# 1-RF.net
KiCad netlist of a schematic drawn in Altium Designer
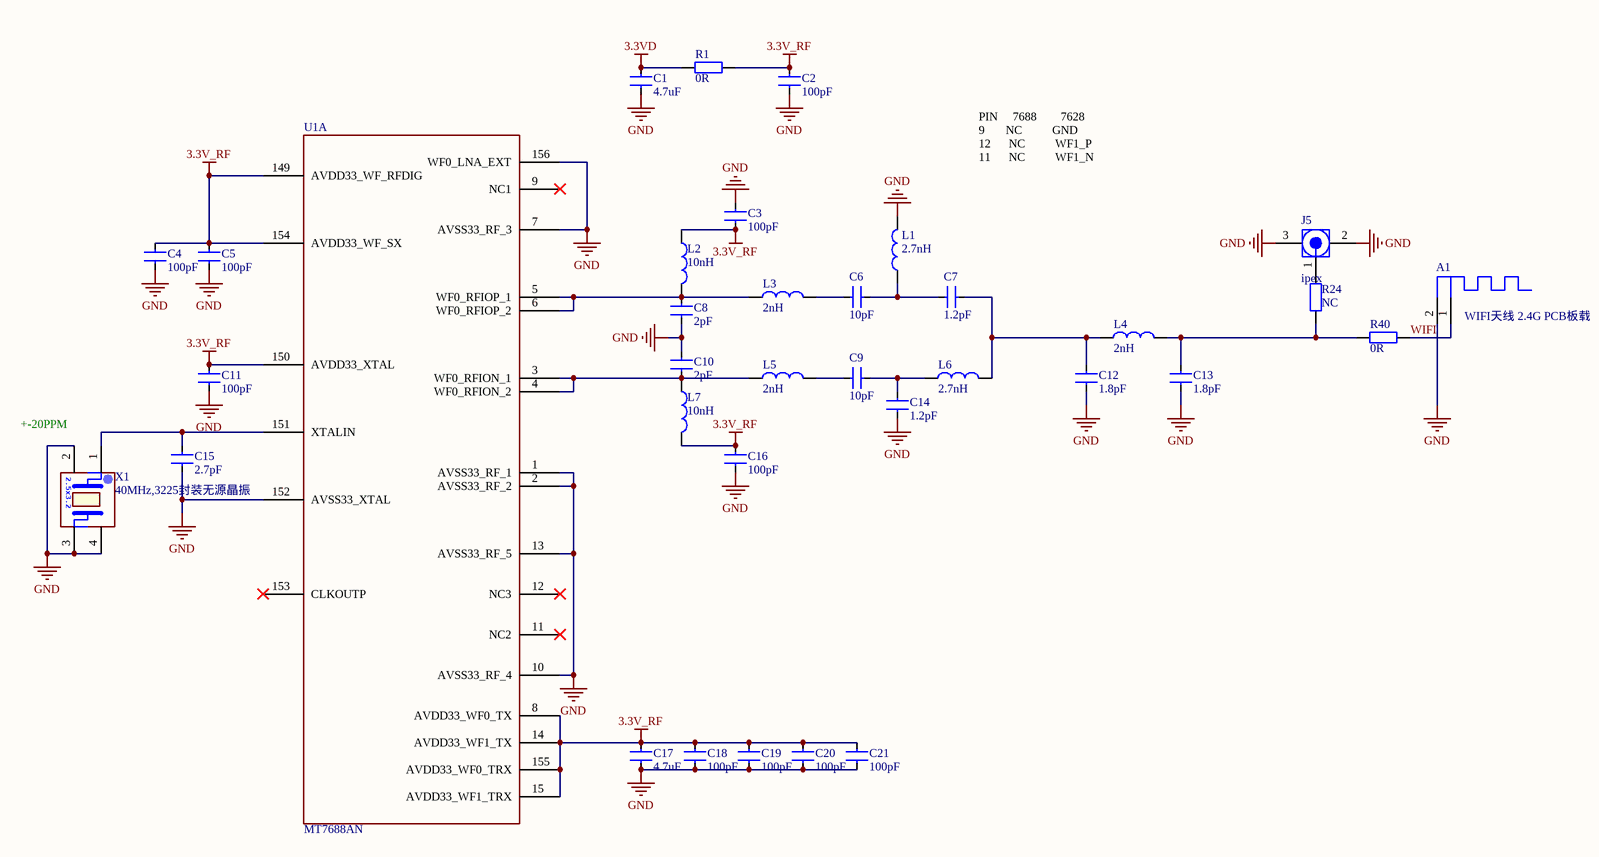
[diagram p0: 1-RF.SchDoc]

(export (version "E")
  (design (tool "Eeschema 10.0.6"))
  (components
    (comp (ref "A1")
      (value "WIFI天线 2.4G PCB板载")
      (footprint "2.4G - mirror")
      (libsource (lib "LIB_MANGO") (part "ANT2.4G"))
    )
    (comp (ref "C1")
      (value "4.7uF")
      (footprint "C0402")
      (description "普通小电容")
      (libsource (lib "LIB_MANGO") (part "CAP"))
    )
    (comp (ref "C2")
      (value "100pF")
      (footprint "C0402")
      (description "普通小电容")
      (libsource (lib "LIB_MANGO") (part "CAP"))
    )
    (comp (ref "C3")
      (value "100pF")
      (footprint "C0402")
      (description "普通小电容")
      (libsource (lib "LIB_MANGO") (part "CAP"))
    )
    (comp (ref "C4")
      (value "100pF")
      (footprint "C0402")
      (description "普通小电容")
      (libsource (lib "LIB_MANGO") (part "CAP"))
    )
    (comp (ref "C5")
      (value "100pF")
      (footprint "C0402")
      (description "普通小电容")
      (libsource (lib "LIB_MANGO") (part "CAP"))
    )
    (comp (ref "C6")
      (value "10pF")
      (footprint "C0402")
      (description "GRM1555C1H100JA01D,500R07N100JV4")
      (libsource (lib "LIB_MANGO") (part "CAP"))
    )
    (comp (ref "C7")
      (value "1.2pF")
      (footprint "C0402")
      (description "GRM1555C1H1R2CA01D,500R07N1R2CV4")
      (libsource (lib "LIB_MANGO") (part "CAP"))
    )
    (comp (ref "C8")
      (value "2pF")
      (footprint "C0402")
      (description "GRM1555C1H2R0CA01D,500R07N2R0CV4")
      (libsource (lib "LIB_MANGO") (part "CAP"))
    )
    (comp (ref "C9")
      (value "10pF")
      (footprint "C0402")
      (description "GRM1555C1H100JA01D,500R07N100JV4")
      (libsource (lib "LIB_MANGO") (part "CAP"))
    )
    (comp (ref "C10")
      (value "2pF")
      (footprint "C0402")
      (description "GRM1555C1H2R0CA01D,500R07N2R0CV4")
      (libsource (lib "LIB_MANGO") (part "CAP"))
    )
    (comp (ref "C11")
      (value "100pF")
      (footprint "C0402")
      (description "普通小电容")
      (libsource (lib "LIB_MANGO") (part "CAP"))
    )
    (comp (ref "C12")
      (value "1.8pF")
      (footprint "C0402")
      (description "GRM1555C1H1R8CA01D")
      (libsource (lib "LIB_MANGO") (part "CAP"))
    )
    (comp (ref "C13")
      (value "1.8pF")
      (footprint "C0402")
      (description "GRM1555C1H1R8CA01D")
      (libsource (lib "LIB_MANGO") (part "CAP"))
    )
    (comp (ref "C14")
      (value "1.2pF")
      (footprint "C0402")
      (description "GRM1555C1H1R2CA01D,500R07N1R2CV4")
      (libsource (lib "LIB_MANGO") (part "CAP"))
    )
    (comp (ref "C15")
      (value "2.7pF")
      (footprint "C0402")
      (description "普通小电容")
      (libsource (lib "LIB_MANGO") (part "CAP"))
    )
    (comp (ref "C16")
      (value "100pF")
      (footprint "C0402")
      (description "普通小电容")
      (libsource (lib "LIB_MANGO") (part "CAP"))
    )
    (comp (ref "C17")
      (value "4.7uF")
      (footprint "C0402")
      (description "普通小电容")
      (libsource (lib "LIB_MANGO") (part "CAP"))
    )
    (comp (ref "C18")
      (value "100pF")
      (footprint "C0402")
      (description "普通小电容")
      (libsource (lib "LIB_MANGO") (part "CAP"))
    )
    (comp (ref "C19")
      (value "100pF")
      (footprint "C0402")
      (description "普通小电容")
      (libsource (lib "LIB_MANGO") (part "CAP"))
    )
    (comp (ref "C20")
      (value "100pF")
      (footprint "C0402")
      (description "普通小电容")
      (libsource (lib "LIB_MANGO") (part "CAP"))
    )
    (comp (ref "C21")
      (value "100pF")
      (footprint "C0402")
      (description "普通小电容")
      (libsource (lib "LIB_MANGO") (part "CAP"))
    )
    (comp (ref "J5") (value "ipex") (footprint "IPEX") (libsource (lib "LIB_MANGO") (part "MCX_IPEX")))
    (comp (ref "L1")
      (value "2.7nH")
      (footprint "L0402")
      (description "LQG15HS2N7S02,MLG1005S2N7ST")
      (libsource (lib "") (part "L0402_1"))
    )
    (comp (ref "L2")
      (value "10nH")
      (footprint "L0402")
      (description "LQG15HS10NJ02,MLG1005S10NJT,HI1005-1C10NJMT")
      (libsource (lib "") (part "L0402_1"))
    )
    (comp (ref "L3")
      (value "2nH")
      (footprint "L0402")
      (description "LQG15HS2N0S02")
      (libsource (lib "LIB_MANGO") (part "L0402"))
    )
    (comp (ref "L4")
      (value "2nH")
      (footprint "L0402")
      (description "LQG15HS2N0S02")
      (libsource (lib "LIB_MANGO") (part "L0402"))
    )
    (comp (ref "L5")
      (value "2nH")
      (footprint "L0402")
      (description "LQG15HS2N0S02")
      (libsource (lib "LIB_MANGO") (part "L0402"))
    )
    (comp (ref "L6")
      (value "2.7nH")
      (footprint "L0402")
      (description "LQG15HS2N7S02,MLG1005S2N7ST")
      (libsource (lib "LIB_MANGO") (part "L0402"))
    )
    (comp (ref "L7")
      (value "10nH")
      (footprint "L0402")
      (description "LQG15HS10NJ02,MLG1005S10NJT,HI1005-1C10NJMT")
      (libsource (lib "") (part "L0402_1"))
    )
    (comp (ref "R1")
      (value "0R")
      (footprint "R0402")
      (description "普通电阻")
      (libsource (lib "LIB_MANGO") (part "RES"))
    )
    (comp (ref "R24")
      (value "NC")
      (footprint "R0402")
      (description "普通电阻")
      (libsource (lib "") (part "RES_1"))
    )
    (comp (ref "R40")
      (value "0R")
      (footprint "R0402")
      (description "普通电阻")
      (libsource (lib "LIB_MANGO") (part "RES"))
    )
    (comp (ref "U1")
      (value "MT7688AN")
      (footprint "MT7628AN/DRQFN156/SMD/P0.5/12X12")
      (libsource (lib "A") (part "MT7688AN"))
    )
    (comp (ref "X1")
      (value "40MHz,3225封装无源晶振")
      (footprint "XTAL3225")
      (description "贴片晶振")
      (libsource (lib "RCLD") (part "XTAL3225"))
    )
  )
  (nets
    (net (code "1") (name "/WIFI") (class "Default")
      (node (ref "A1") (pin "1") (pintype "passive"))
      (node (ref "R40") (pin "2") (pinfunction "2_2") (pintype "passive"))
    )
    (net (code "2") (name "3.3VD") (class "Default")
      (node (ref "C1") (pin "1") (pinfunction "1_1") (pintype "passive"))
      (node (ref "R1") (pin "1") (pinfunction "1_1") (pintype "passive"))
    )
    (net (code "3") (name "3.3V_RF") (class "Default")
      (node (ref "C11") (pin "1") (pinfunction "1_1") (pintype "passive"))
      (node (ref "C16") (pin "1") (pinfunction "1_1") (pintype "passive"))
      (node (ref "C17") (pin "1") (pinfunction "1_1") (pintype "passive"))
      (node (ref "C18") (pin "1") (pinfunction "1_1") (pintype "passive"))
      (node (ref "C19") (pin "1") (pinfunction "1_1") (pintype "passive"))
      (node (ref "C2") (pin "1") (pinfunction "1_1") (pintype "passive"))
      (node (ref "C20") (pin "1") (pinfunction "1_1") (pintype "passive"))
      (node (ref "C21") (pin "1") (pinfunction "1_1") (pintype "passive"))
      (node (ref "C3") (pin "2") (pinfunction "2_2") (pintype "passive"))
      (node (ref "C4") (pin "1") (pinfunction "1_1") (pintype "passive"))
      (node (ref "C5") (pin "1") (pinfunction "1_1") (pintype "passive"))
      (node (ref "L2") (pin "2") (pinfunction "2_2") (pintype "passive"))
      (node (ref "L7") (pin "1") (pinfunction "1_1") (pintype "passive"))
      (node (ref "R1") (pin "2") (pinfunction "2_2") (pintype "passive"))
      (node (ref "U1") (pin "14") (pinfunction "AVDD33_WF1_TX_14") (pintype "passive"))
      (node (ref "U1") (pin "149") (pinfunction "AVDD33_WF_RFDIG_149") (pintype "passive"))
      (node (ref "U1") (pin "15") (pinfunction "AVDD33_WF1_TRX_15") (pintype "passive"))
      (node (ref "U1") (pin "150") (pinfunction "AVDD33_XTAL_150") (pintype "passive"))
      (node (ref "U1") (pin "154") (pinfunction "AVDD33_WF_SX_154") (pintype "passive"))
      (node (ref "U1") (pin "155") (pinfunction "AVDD33_WF0_TRX_155") (pintype "passive"))
      (node (ref "U1") (pin "8") (pinfunction "AVDD33_WF0_TX_8") (pintype "passive"))
    )
    (net (code "4") (name "GND") (class "Default")
      (node (ref "A1") (pin "2") (pinfunction "G_2") (pintype "passive"))
      (node (ref "C1") (pin "2") (pinfunction "2_2") (pintype "passive"))
      (node (ref "C10") (pin "1") (pinfunction "1_1") (pintype "passive"))
      (node (ref "C11") (pin "2") (pinfunction "2_2") (pintype "passive"))
      (node (ref "C12") (pin "2") (pinfunction "2_2") (pintype "passive"))
      (node (ref "C13") (pin "2") (pinfunction "2_2") (pintype "passive"))
      (node (ref "C14") (pin "1") (pinfunction "1_1") (pintype "passive"))
      (node (ref "C15") (pin "1") (pinfunction "1_1") (pintype "passive"))
      (node (ref "C16") (pin "2") (pinfunction "2_2") (pintype "passive"))
      (node (ref "C17") (pin "2") (pinfunction "2_2") (pintype "passive"))
      (node (ref "C18") (pin "2") (pinfunction "2_2") (pintype "passive"))
      (node (ref "C19") (pin "2") (pinfunction "2_2") (pintype "passive"))
      (node (ref "C2") (pin "2") (pinfunction "2_2") (pintype "passive"))
      (node (ref "C20") (pin "2") (pinfunction "2_2") (pintype "passive"))
      (node (ref "C21") (pin "2") (pinfunction "2_2") (pintype "passive"))
      (node (ref "C3") (pin "1") (pinfunction "1_1") (pintype "passive"))
      (node (ref "C4") (pin "2") (pinfunction "2_2") (pintype "passive"))
      (node (ref "C5") (pin "2") (pinfunction "2_2") (pintype "passive"))
      (node (ref "C8") (pin "2") (pinfunction "2_2") (pintype "passive"))
      (node (ref "J5") (pin "2") (pinfunction "GND_2") (pintype "power_in"))
      (node (ref "J5") (pin "3") (pinfunction "GND_3") (pintype "power_in"))
      (node (ref "L1") (pin "1") (pinfunction "1_1") (pintype "passive"))
      (node (ref "U1") (pin "1") (pinfunction "AVSS33_RF_1_1") (pintype "passive"))
      (node (ref "U1") (pin "10") (pinfunction "AVSS33_RF_4_10") (pintype "passive"))
      (node (ref "U1") (pin "13") (pinfunction "AVSS33_RF_5_13") (pintype "passive"))
      (node (ref "U1") (pin "152") (pinfunction "AVSS33_XTAL_152") (pintype "passive"))
      (node (ref "U1") (pin "156") (pinfunction "WF0_LNA_EXT_156") (pintype "passive"))
      (node (ref "U1") (pin "2") (pinfunction "AVSS33_RF_2_2") (pintype "passive"))
      (node (ref "U1") (pin "7") (pinfunction "AVSS33_RF_3_7") (pintype "passive"))
      (node (ref "X1") (pin "2") (pinfunction "NC1_2") (pintype "passive"))
      (node (ref "X1") (pin "3") (pinfunction "X2_3") (pintype "passive"))
      (node (ref "X1") (pin "4") (pinfunction "NC2_4") (pintype "passive"))
    )
    (net (code "5") (name "Net-(C6-Pad1)") (class "Default")
      (node (ref "C6") (pin "1") (pinfunction "1_1") (pintype "passive"))
      (node (ref "L3") (pin "1") (pinfunction "1_1") (pintype "passive"))
    )
    (net (code "6") (name "Net-(C6-Pad2)") (class "Default")
      (node (ref "C6") (pin "2") (pinfunction "2_2") (pintype "passive"))
      (node (ref "C7") (pin "2") (pinfunction "2_2") (pintype "passive"))
      (node (ref "L1") (pin "2") (pinfunction "2_2") (pintype "passive"))
    )
    (net (code "7") (name "Net-(C9-Pad1)") (class "Default")
      (node (ref "C9") (pin "1") (pinfunction "1_1") (pintype "passive"))
      (node (ref "L5") (pin "1") (pinfunction "1_1") (pintype "passive"))
    )
    (net (code "8") (name "Net-(C12-Pad1)") (class "Default")
      (node (ref "C12") (pin "1") (pinfunction "1_1") (pintype "passive"))
      (node (ref "C7") (pin "1") (pinfunction "1_1") (pintype "passive"))
      (node (ref "L4") (pin "2") (pinfunction "2_2") (pintype "passive"))
      (node (ref "L6") (pin "1") (pinfunction "1_1") (pintype "passive"))
    )
    (net (code "9") (name "Net-(C13-Pad1)") (class "Default")
      (node (ref "C13") (pin "1") (pinfunction "1_1") (pintype "passive"))
      (node (ref "L4") (pin "1") (pinfunction "1_1") (pintype "passive"))
      (node (ref "R24") (pin "1") (pinfunction "1_1") (pintype "passive"))
      (node (ref "R40") (pin "1") (pinfunction "1_1") (pintype "passive"))
    )
    (net (code "10") (name "Net-(C14-Pad2)") (class "Default")
      (node (ref "C14") (pin "2") (pinfunction "2_2") (pintype "passive"))
      (node (ref "C9") (pin "2") (pinfunction "2_2") (pintype "passive"))
      (node (ref "L6") (pin "2") (pinfunction "2_2") (pintype "passive"))
    )
    (net (code "11") (name "Net-(J5-Signal)") (class "Default")
      (node (ref "J5") (pin "1") (pinfunction "Signal_1") (pintype "passive"))
      (node (ref "R24") (pin "2") (pinfunction "2_2") (pintype "passive"))
    )
    (net (code "12") (name "Net-(U1A-WF0_RFION_1)") (class "Default")
      (node (ref "C10") (pin "2") (pinfunction "2_2") (pintype "passive"))
      (node (ref "L5") (pin "2") (pinfunction "2_2") (pintype "passive"))
      (node (ref "L7") (pin "2") (pinfunction "2_2") (pintype "passive"))
      (node (ref "U1") (pin "3") (pinfunction "WF0_RFION_1_3") (pintype "passive"))
      (node (ref "U1") (pin "4") (pinfunction "WF0_RFION_2_4") (pintype "passive"))
    )
    (net (code "13") (name "Net-(U1A-WF0_RFIOP_1)") (class "Default")
      (node (ref "C8") (pin "1") (pinfunction "1_1") (pintype "passive"))
      (node (ref "L2") (pin "1") (pinfunction "1_1") (pintype "passive"))
      (node (ref "L3") (pin "2") (pinfunction "2_2") (pintype "passive"))
      (node (ref "U1") (pin "5") (pinfunction "WF0_RFIOP_1_5") (pintype "passive"))
      (node (ref "U1") (pin "6") (pinfunction "WF0_RFIOP_2_6") (pintype "passive"))
    )
    (net (code "14") (name "Net-(U1A-XTALIN)") (class "Default")
      (node (ref "C15") (pin "2") (pinfunction "2_2") (pintype "passive"))
      (node (ref "U1") (pin "151") (pinfunction "XTALIN_151") (pintype "passive"))
      (node (ref "X1") (pin "1") (pinfunction "X1_1") (pintype "passive"))
    )
    (net (code "15") (name "unconnected-(U1A-CLKOUTP-Pad153)") (class "Default")
      (node (ref "U1") (pin "153") (pinfunction "CLKOUTP_153") (pintype "passive+no_connect"))
    )
    (net (code "16") (name "unconnected-(U1A-NC1-Pad9)") (class "Default")
      (node (ref "U1") (pin "9") (pinfunction "NC1_9") (pintype "passive+no_connect"))
    )
    (net (code "17") (name "unconnected-(U1A-NC2-Pad11)") (class "Default")
      (node (ref "U1") (pin "11") (pinfunction "NC2_11") (pintype "passive+no_connect"))
    )
    (net (code "18") (name "unconnected-(U1A-NC3-Pad12)") (class "Default")
      (node (ref "U1") (pin "12") (pinfunction "NC3_12") (pintype "passive+no_connect"))
    )
  )
)
